# con-left-top.net
KiCad netlist of a schematic drawn in Altium Designer
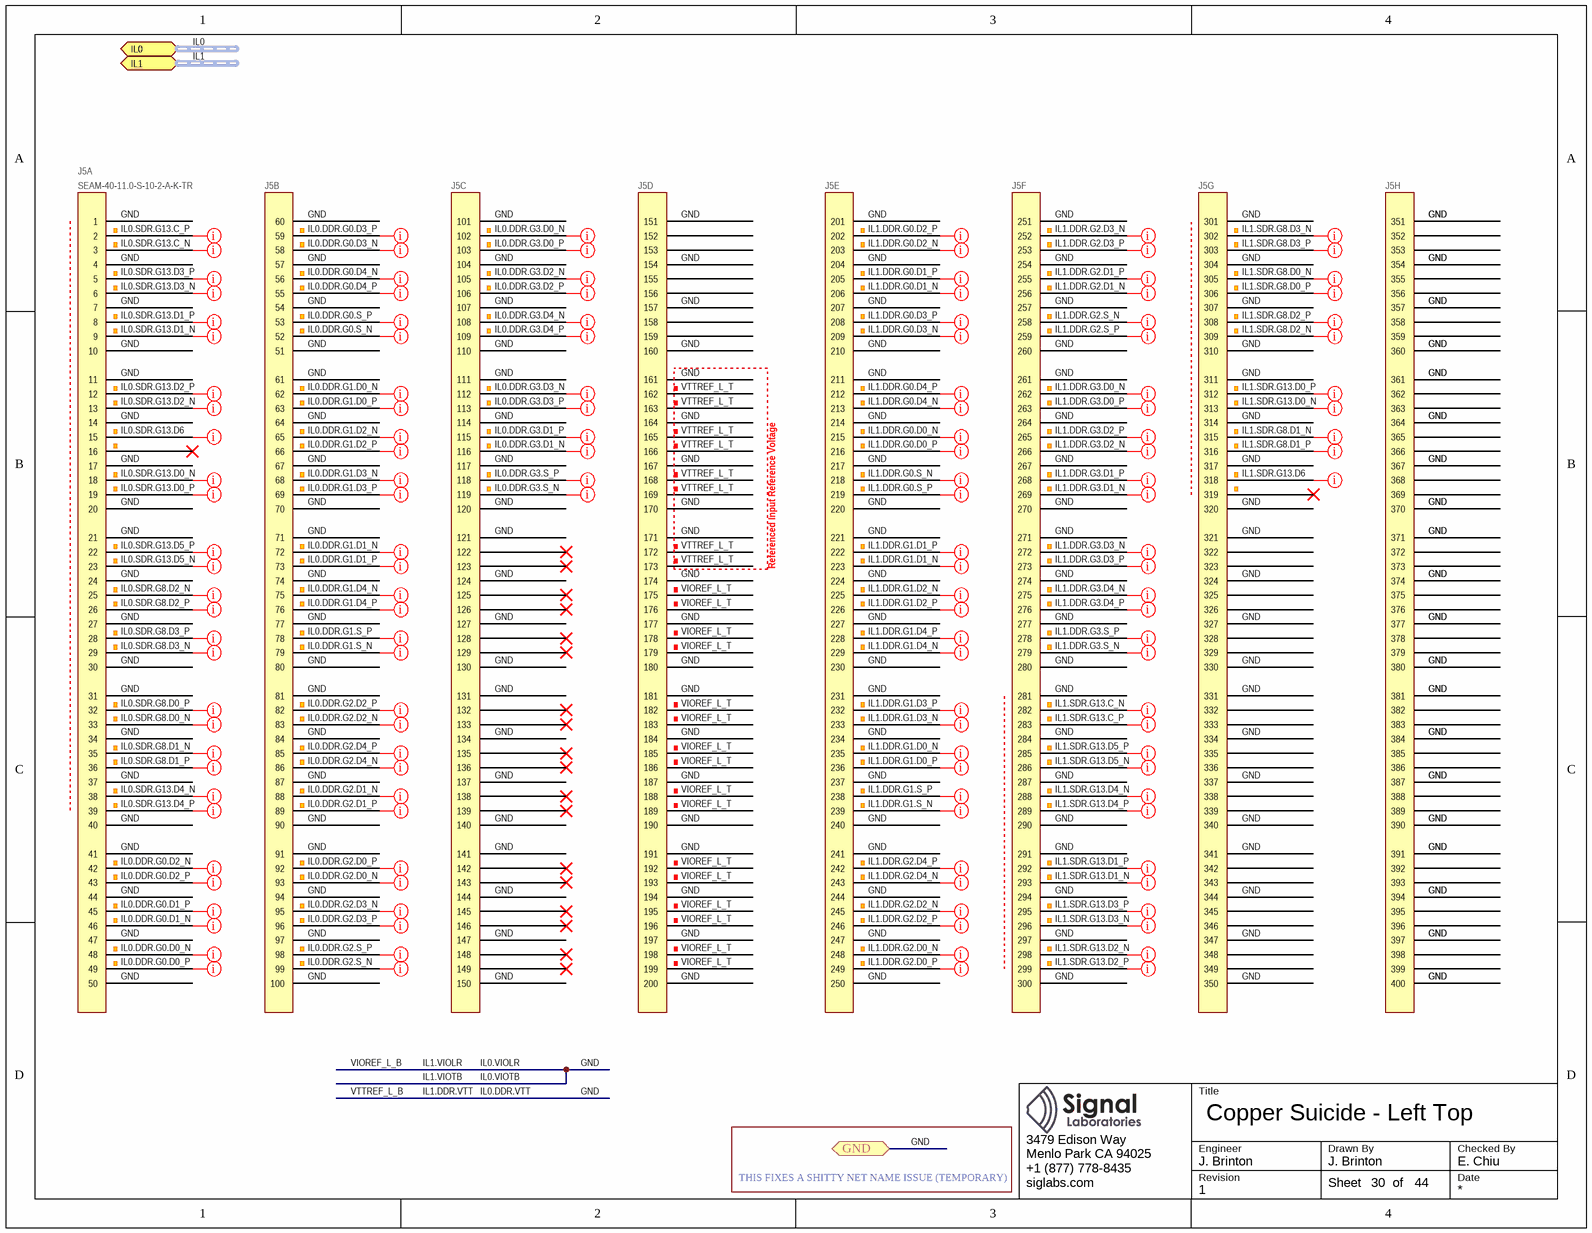
[diagram p0: con-left-top.SchDoc]

(export (version "E")
  (design (tool "Eeschema 10.0.6"))
  (components
    (comp (ref "J5")
      (value "SEAM-40-11.0-S-10-2-A-K-TR")
      (footprint "samtec:SEAM-40-11.0-S-10-2-A-K-TR")
      (description "Terminal Array Assembly, Surface Mount, 0.050\" Pitch, 400 Pins")
      (fields (field (name "MANUFACTURER") "Samtec"))
      (libsource (lib "samtec") (part "SEAM-40-11.0-S-10-2-A-K-TR"))
    )
  )
  (nets
    (net (code "3") (name "/GND") (class "Default")
      (node (ref "J5") (pin "1") (pinfunction "1_1") (pintype "passive"))
      (node (ref "J5") (pin "10") (pinfunction "10_10") (pintype "passive"))
      (node (ref "J5") (pin "100") (pinfunction "100_100") (pintype "passive"))
      (node (ref "J5") (pin "101") (pinfunction "101_101") (pintype "passive"))
      (node (ref "J5") (pin "104") (pinfunction "104_104") (pintype "passive"))
      (node (ref "J5") (pin "107") (pinfunction "107_107") (pintype "passive"))
      (node (ref "J5") (pin "11") (pinfunction "11_11") (pintype "passive"))
      (node (ref "J5") (pin "110") (pinfunction "110_110") (pintype "passive"))
      (node (ref "J5") (pin "111") (pinfunction "111_111") (pintype "passive"))
      (node (ref "J5") (pin "114") (pinfunction "114_114") (pintype "passive"))
      (node (ref "J5") (pin "117") (pinfunction "117_117") (pintype "passive"))
      (node (ref "J5") (pin "120") (pinfunction "120_120") (pintype "passive"))
      (node (ref "J5") (pin "121") (pinfunction "121_121") (pintype "passive"))
      (node (ref "J5") (pin "124") (pinfunction "124_124") (pintype "passive"))
      (node (ref "J5") (pin "127") (pinfunction "127_127") (pintype "passive"))
      (node (ref "J5") (pin "130") (pinfunction "130_130") (pintype "passive"))
      (node (ref "J5") (pin "131") (pinfunction "131_131") (pintype "passive"))
      (node (ref "J5") (pin "134") (pinfunction "134_134") (pintype "passive"))
      (node (ref "J5") (pin "137") (pinfunction "137_137") (pintype "passive"))
      (node (ref "J5") (pin "14") (pinfunction "14_14") (pintype "passive"))
      (node (ref "J5") (pin "140") (pinfunction "140_140") (pintype "passive"))
      (node (ref "J5") (pin "141") (pinfunction "141_141") (pintype "passive"))
      (node (ref "J5") (pin "144") (pinfunction "144_144") (pintype "passive"))
      (node (ref "J5") (pin "147") (pinfunction "147_147") (pintype "passive"))
      (node (ref "J5") (pin "150") (pinfunction "150_150") (pintype "passive"))
      (node (ref "J5") (pin "151") (pinfunction "151_151") (pintype "passive"))
      (node (ref "J5") (pin "154") (pinfunction "154_154") (pintype "passive"))
      (node (ref "J5") (pin "157") (pinfunction "157_157") (pintype "passive"))
      (node (ref "J5") (pin "160") (pinfunction "160_160") (pintype "passive"))
      (node (ref "J5") (pin "161") (pinfunction "161_161") (pintype "passive"))
      (node (ref "J5") (pin "164") (pinfunction "164_164") (pintype "passive"))
      (node (ref "J5") (pin "167") (pinfunction "167_167") (pintype "passive"))
      (node (ref "J5") (pin "17") (pinfunction "17_17") (pintype "passive"))
      (node (ref "J5") (pin "170") (pinfunction "170_170") (pintype "passive"))
      (node (ref "J5") (pin "171") (pinfunction "171_171") (pintype "passive"))
      (node (ref "J5") (pin "174") (pinfunction "174_174") (pintype "passive"))
      (node (ref "J5") (pin "177") (pinfunction "177_177") (pintype "passive"))
      (node (ref "J5") (pin "180") (pinfunction "180_180") (pintype "passive"))
      (node (ref "J5") (pin "181") (pinfunction "181_181") (pintype "passive"))
      (node (ref "J5") (pin "184") (pinfunction "184_184") (pintype "passive"))
      (node (ref "J5") (pin "187") (pinfunction "187_187") (pintype "passive"))
      (node (ref "J5") (pin "190") (pinfunction "190_190") (pintype "passive"))
      (node (ref "J5") (pin "191") (pinfunction "191_191") (pintype "passive"))
      (node (ref "J5") (pin "194") (pinfunction "194_194") (pintype "passive"))
      (node (ref "J5") (pin "197") (pinfunction "197_197") (pintype "passive"))
      (node (ref "J5") (pin "20") (pinfunction "20_20") (pintype "passive"))
      (node (ref "J5") (pin "200") (pinfunction "200_200") (pintype "passive"))
      (node (ref "J5") (pin "201") (pinfunction "201_201") (pintype "passive"))
      (node (ref "J5") (pin "204") (pinfunction "204_204") (pintype "passive"))
      (node (ref "J5") (pin "207") (pinfunction "207_207") (pintype "passive"))
      (node (ref "J5") (pin "21") (pinfunction "21_21") (pintype "passive"))
      (node (ref "J5") (pin "210") (pinfunction "210_210") (pintype "passive"))
      (node (ref "J5") (pin "211") (pinfunction "211_211") (pintype "passive"))
      (node (ref "J5") (pin "214") (pinfunction "214_214") (pintype "passive"))
      (node (ref "J5") (pin "217") (pinfunction "217_217") (pintype "passive"))
      (node (ref "J5") (pin "220") (pinfunction "220_220") (pintype "passive"))
      (node (ref "J5") (pin "221") (pinfunction "221_221") (pintype "passive"))
      (node (ref "J5") (pin "224") (pinfunction "224_224") (pintype "passive"))
      (node (ref "J5") (pin "227") (pinfunction "227_227") (pintype "passive"))
      (node (ref "J5") (pin "230") (pinfunction "230_230") (pintype "passive"))
      (node (ref "J5") (pin "231") (pinfunction "231_231") (pintype "passive"))
      (node (ref "J5") (pin "234") (pinfunction "234_234") (pintype "passive"))
      (node (ref "J5") (pin "237") (pinfunction "237_237") (pintype "passive"))
      (node (ref "J5") (pin "24") (pinfunction "24_24") (pintype "passive"))
      (node (ref "J5") (pin "240") (pinfunction "240_240") (pintype "passive"))
      (node (ref "J5") (pin "241") (pinfunction "241_241") (pintype "passive"))
      (node (ref "J5") (pin "244") (pinfunction "244_244") (pintype "passive"))
      (node (ref "J5") (pin "247") (pinfunction "247_247") (pintype "passive"))
      (node (ref "J5") (pin "250") (pinfunction "250_250") (pintype "passive"))
      (node (ref "J5") (pin "251") (pinfunction "251_251") (pintype "passive"))
      (node (ref "J5") (pin "254") (pinfunction "254_254") (pintype "passive"))
      (node (ref "J5") (pin "257") (pinfunction "257_257") (pintype "passive"))
      (node (ref "J5") (pin "260") (pinfunction "260_260") (pintype "passive"))
      (node (ref "J5") (pin "261") (pinfunction "261_261") (pintype "passive"))
      (node (ref "J5") (pin "264") (pinfunction "264_264") (pintype "passive"))
      (node (ref "J5") (pin "267") (pinfunction "267_267") (pintype "passive"))
      (node (ref "J5") (pin "27") (pinfunction "27_27") (pintype "passive"))
      (node (ref "J5") (pin "270") (pinfunction "270_270") (pintype "passive"))
      (node (ref "J5") (pin "271") (pinfunction "271_271") (pintype "passive"))
      (node (ref "J5") (pin "274") (pinfunction "274_274") (pintype "passive"))
      (node (ref "J5") (pin "277") (pinfunction "277_277") (pintype "passive"))
      (node (ref "J5") (pin "280") (pinfunction "280_280") (pintype "passive"))
      (node (ref "J5") (pin "281") (pinfunction "281_281") (pintype "passive"))
      (node (ref "J5") (pin "284") (pinfunction "284_284") (pintype "passive"))
      (node (ref "J5") (pin "287") (pinfunction "287_287") (pintype "passive"))
      (node (ref "J5") (pin "290") (pinfunction "290_290") (pintype "passive"))
      (node (ref "J5") (pin "291") (pinfunction "291_291") (pintype "passive"))
      (node (ref "J5") (pin "294") (pinfunction "294_294") (pintype "passive"))
      (node (ref "J5") (pin "297") (pinfunction "297_297") (pintype "passive"))
      (node (ref "J5") (pin "30") (pinfunction "30_30") (pintype "passive"))
      (node (ref "J5") (pin "300") (pinfunction "300_300") (pintype "passive"))
      (node (ref "J5") (pin "301") (pinfunction "301_301") (pintype "passive"))
      (node (ref "J5") (pin "304") (pinfunction "304_304") (pintype "passive"))
      (node (ref "J5") (pin "307") (pinfunction "307_307") (pintype "passive"))
      (node (ref "J5") (pin "31") (pinfunction "31_31") (pintype "passive"))
      (node (ref "J5") (pin "310") (pinfunction "310_310") (pintype "passive"))
      (node (ref "J5") (pin "311") (pinfunction "311_311") (pintype "passive"))
      (node (ref "J5") (pin "314") (pinfunction "314_314") (pintype "passive"))
      (node (ref "J5") (pin "317") (pinfunction "317_317") (pintype "passive"))
      (node (ref "J5") (pin "320") (pinfunction "320_320") (pintype "passive"))
      (node (ref "J5") (pin "321") (pinfunction "321_321") (pintype "passive"))
      (node (ref "J5") (pin "324") (pinfunction "324_324") (pintype "passive"))
      (node (ref "J5") (pin "327") (pinfunction "327_327") (pintype "passive"))
      (node (ref "J5") (pin "330") (pinfunction "330_330") (pintype "passive"))
      (node (ref "J5") (pin "331") (pinfunction "331_331") (pintype "passive"))
      (node (ref "J5") (pin "334") (pinfunction "334_334") (pintype "passive"))
      (node (ref "J5") (pin "337") (pinfunction "337_337") (pintype "passive"))
      (node (ref "J5") (pin "34") (pinfunction "34_34") (pintype "passive"))
      (node (ref "J5") (pin "340") (pinfunction "340_340") (pintype "passive"))
      (node (ref "J5") (pin "341") (pinfunction "341_341") (pintype "passive"))
      (node (ref "J5") (pin "344") (pinfunction "344_344") (pintype "passive"))
      (node (ref "J5") (pin "347") (pinfunction "347_347") (pintype "passive"))
      (node (ref "J5") (pin "350") (pinfunction "350_350") (pintype "passive"))
      (node (ref "J5") (pin "351") (pinfunction "351_351") (pintype "passive"))
      (node (ref "J5") (pin "354") (pinfunction "354_354") (pintype "passive"))
      (node (ref "J5") (pin "357") (pinfunction "357_357") (pintype "passive"))
      (node (ref "J5") (pin "360") (pinfunction "360_360") (pintype "passive"))
      (node (ref "J5") (pin "361") (pinfunction "361_361") (pintype "passive"))
      (node (ref "J5") (pin "364") (pinfunction "364_364") (pintype "passive"))
      (node (ref "J5") (pin "367") (pinfunction "367_367") (pintype "passive"))
      (node (ref "J5") (pin "37") (pinfunction "37_37") (pintype "passive"))
      (node (ref "J5") (pin "370") (pinfunction "370_370") (pintype "passive"))
      (node (ref "J5") (pin "371") (pinfunction "371_371") (pintype "passive"))
      (node (ref "J5") (pin "374") (pinfunction "374_374") (pintype "passive"))
      (node (ref "J5") (pin "377") (pinfunction "377_377") (pintype "passive"))
      (node (ref "J5") (pin "380") (pinfunction "380_380") (pintype "passive"))
      (node (ref "J5") (pin "381") (pinfunction "381_381") (pintype "passive"))
      (node (ref "J5") (pin "384") (pinfunction "384_384") (pintype "passive"))
      (node (ref "J5") (pin "387") (pinfunction "387_387") (pintype "passive"))
      (node (ref "J5") (pin "390") (pinfunction "390_390") (pintype "passive"))
      (node (ref "J5") (pin "391") (pinfunction "391_391") (pintype "passive"))
      (node (ref "J5") (pin "394") (pinfunction "394_394") (pintype "passive"))
      (node (ref "J5") (pin "397") (pinfunction "397_397") (pintype "passive"))
      (node (ref "J5") (pin "4") (pinfunction "4_4") (pintype "passive"))
      (node (ref "J5") (pin "40") (pinfunction "40_40") (pintype "passive"))
      (node (ref "J5") (pin "400") (pinfunction "400_400") (pintype "passive"))
      (node (ref "J5") (pin "41") (pinfunction "41_41") (pintype "passive"))
      (node (ref "J5") (pin "44") (pinfunction "44_44") (pintype "passive"))
      (node (ref "J5") (pin "47") (pinfunction "47_47") (pintype "passive"))
      (node (ref "J5") (pin "50") (pinfunction "50_50") (pintype "passive"))
      (node (ref "J5") (pin "51") (pinfunction "51_51") (pintype "passive"))
      (node (ref "J5") (pin "54") (pinfunction "54_54") (pintype "passive"))
      (node (ref "J5") (pin "57") (pinfunction "57_57") (pintype "passive"))
      (node (ref "J5") (pin "60") (pinfunction "60_60") (pintype "passive"))
      (node (ref "J5") (pin "61") (pinfunction "61_61") (pintype "passive"))
      (node (ref "J5") (pin "64") (pinfunction "64_64") (pintype "passive"))
      (node (ref "J5") (pin "67") (pinfunction "67_67") (pintype "passive"))
      (node (ref "J5") (pin "7") (pinfunction "7_7") (pintype "passive"))
      (node (ref "J5") (pin "70") (pinfunction "70_70") (pintype "passive"))
      (node (ref "J5") (pin "71") (pinfunction "71_71") (pintype "passive"))
      (node (ref "J5") (pin "74") (pinfunction "74_74") (pintype "passive"))
      (node (ref "J5") (pin "77") (pinfunction "77_77") (pintype "passive"))
      (node (ref "J5") (pin "80") (pinfunction "80_80") (pintype "passive"))
      (node (ref "J5") (pin "81") (pinfunction "81_81") (pintype "passive"))
      (node (ref "J5") (pin "84") (pinfunction "84_84") (pintype "passive"))
      (node (ref "J5") (pin "87") (pinfunction "87_87") (pintype "passive"))
      (node (ref "J5") (pin "90") (pinfunction "90_90") (pintype "passive"))
      (node (ref "J5") (pin "91") (pinfunction "91_91") (pintype "passive"))
      (node (ref "J5") (pin "94") (pinfunction "94_94") (pintype "passive"))
      (node (ref "J5") (pin "97") (pinfunction "97_97") (pintype "passive"))
    )
    (net (code "4") (name "/IL0.DDR.G0.D0_N") (class "Default")
      (node (ref "J5") (pin "48") (pinfunction "48_48") (pintype "passive"))
    )
    (net (code "5") (name "/IL0.DDR.G0.D0_P") (class "Default")
      (node (ref "J5") (pin "49") (pinfunction "49_49") (pintype "passive"))
    )
    (net (code "6") (name "/IL0.DDR.G0.D1_N") (class "Default")
      (node (ref "J5") (pin "46") (pinfunction "46_46") (pintype "passive"))
    )
    (net (code "7") (name "/IL0.DDR.G0.D1_P") (class "Default")
      (node (ref "J5") (pin "45") (pinfunction "45_45") (pintype "passive"))
    )
    (net (code "8") (name "/IL0.DDR.G0.D2_N") (class "Default")
      (node (ref "J5") (pin "42") (pinfunction "42_42") (pintype "passive"))
    )
    (net (code "9") (name "/IL0.DDR.G0.D2_P") (class "Default")
      (node (ref "J5") (pin "43") (pinfunction "43_43") (pintype "passive"))
    )
    (net (code "10") (name "/IL0.DDR.G0.D3_N") (class "Default")
      (node (ref "J5") (pin "58") (pinfunction "58_58") (pintype "passive"))
    )
    (net (code "11") (name "/IL0.DDR.G0.D3_P") (class "Default")
      (node (ref "J5") (pin "59") (pinfunction "59_59") (pintype "passive"))
    )
    (net (code "12") (name "/IL0.DDR.G0.D4_N") (class "Default")
      (node (ref "J5") (pin "56") (pinfunction "56_56") (pintype "passive"))
    )
    (net (code "13") (name "/IL0.DDR.G0.D4_P") (class "Default")
      (node (ref "J5") (pin "55") (pinfunction "55_55") (pintype "passive"))
    )
    (net (code "14") (name "/IL0.DDR.G0.S_N") (class "Default")
      (node (ref "J5") (pin "52") (pinfunction "52_52") (pintype "passive"))
    )
    (net (code "15") (name "/IL0.DDR.G0.S_P") (class "Default")
      (node (ref "J5") (pin "53") (pinfunction "53_53") (pintype "passive"))
    )
    (net (code "16") (name "/IL0.DDR.G1.D0_N") (class "Default")
      (node (ref "J5") (pin "62") (pinfunction "62_62") (pintype "passive"))
    )
    (net (code "17") (name "/IL0.DDR.G1.D0_P") (class "Default")
      (node (ref "J5") (pin "63") (pinfunction "63_63") (pintype "passive"))
    )
    (net (code "18") (name "/IL0.DDR.G1.D1_N") (class "Default")
      (node (ref "J5") (pin "72") (pinfunction "72_72") (pintype "passive"))
    )
    (net (code "19") (name "/IL0.DDR.G1.D1_P") (class "Default")
      (node (ref "J5") (pin "73") (pinfunction "73_73") (pintype "passive"))
    )
    (net (code "20") (name "/IL0.DDR.G1.D2_N") (class "Default")
      (node (ref "J5") (pin "65") (pinfunction "65_65") (pintype "passive"))
    )
    (net (code "21") (name "/IL0.DDR.G1.D2_P") (class "Default")
      (node (ref "J5") (pin "66") (pinfunction "66_66") (pintype "passive"))
    )
    (net (code "22") (name "/IL0.DDR.G1.D3_N") (class "Default")
      (node (ref "J5") (pin "68") (pinfunction "68_68") (pintype "passive"))
    )
    (net (code "23") (name "/IL0.DDR.G1.D3_P") (class "Default")
      (node (ref "J5") (pin "69") (pinfunction "69_69") (pintype "passive"))
    )
    (net (code "24") (name "/IL0.DDR.G1.D4_N") (class "Default")
      (node (ref "J5") (pin "75") (pinfunction "75_75") (pintype "passive"))
    )
    (net (code "25") (name "/IL0.DDR.G1.D4_P") (class "Default")
      (node (ref "J5") (pin "76") (pinfunction "76_76") (pintype "passive"))
    )
    (net (code "26") (name "/IL0.DDR.G1.S_N") (class "Default")
      (node (ref "J5") (pin "79") (pinfunction "79_79") (pintype "passive"))
    )
    (net (code "27") (name "/IL0.DDR.G1.S_P") (class "Default")
      (node (ref "J5") (pin "78") (pinfunction "78_78") (pintype "passive"))
    )
    (net (code "28") (name "/IL0.DDR.G2.D0_N") (class "Default")
      (node (ref "J5") (pin "93") (pinfunction "93_93") (pintype "passive"))
    )
    (net (code "29") (name "/IL0.DDR.G2.D0_P") (class "Default")
      (node (ref "J5") (pin "92") (pinfunction "92_92") (pintype "passive"))
    )
    (net (code "30") (name "/IL0.DDR.G2.D1_N") (class "Default")
      (node (ref "J5") (pin "88") (pinfunction "88_88") (pintype "passive"))
    )
    (net (code "31") (name "/IL0.DDR.G2.D1_P") (class "Default")
      (node (ref "J5") (pin "89") (pinfunction "89_89") (pintype "passive"))
    )
    (net (code "32") (name "/IL0.DDR.G2.D2_N") (class "Default")
      (node (ref "J5") (pin "83") (pinfunction "83_83") (pintype "passive"))
    )
    (net (code "33") (name "/IL0.DDR.G2.D2_P") (class "Default")
      (node (ref "J5") (pin "82") (pinfunction "82_82") (pintype "passive"))
    )
    (net (code "34") (name "/IL0.DDR.G2.D3_N") (class "Default")
      (node (ref "J5") (pin "95") (pinfunction "95_95") (pintype "passive"))
    )
    (net (code "35") (name "/IL0.DDR.G2.D3_P") (class "Default")
      (node (ref "J5") (pin "96") (pinfunction "96_96") (pintype "passive"))
    )
    (net (code "36") (name "/IL0.DDR.G2.D4_N") (class "Default")
      (node (ref "J5") (pin "86") (pinfunction "86_86") (pintype "passive"))
    )
    (net (code "37") (name "/IL0.DDR.G2.D4_P") (class "Default")
      (node (ref "J5") (pin "85") (pinfunction "85_85") (pintype "passive"))
    )
    (net (code "38") (name "/IL0.DDR.G2.S_N") (class "Default")
      (node (ref "J5") (pin "99") (pinfunction "99_99") (pintype "passive"))
    )
    (net (code "39") (name "/IL0.DDR.G2.S_P") (class "Default")
      (node (ref "J5") (pin "98") (pinfunction "98_98") (pintype "passive"))
    )
    (net (code "40") (name "/IL0.DDR.G3.D0_N") (class "Default")
      (node (ref "J5") (pin "102") (pinfunction "102_102") (pintype "passive"))
    )
    (net (code "41") (name "/IL0.DDR.G3.D0_P") (class "Default")
      (node (ref "J5") (pin "103") (pinfunction "103_103") (pintype "passive"))
    )
    (net (code "42") (name "/IL0.DDR.G3.D1_N") (class "Default")
      (node (ref "J5") (pin "116") (pinfunction "116_116") (pintype "passive"))
    )
    (net (code "43") (name "/IL0.DDR.G3.D1_P") (class "Default")
      (node (ref "J5") (pin "115") (pinfunction "115_115") (pintype "passive"))
    )
    (net (code "44") (name "/IL0.DDR.G3.D2_N") (class "Default")
      (node (ref "J5") (pin "105") (pinfunction "105_105") (pintype "passive"))
    )
    (net (code "45") (name "/IL0.DDR.G3.D2_P") (class "Default")
      (node (ref "J5") (pin "106") (pinfunction "106_106") (pintype "passive"))
    )
    (net (code "46") (name "/IL0.DDR.G3.D3_N") (class "Default")
      (node (ref "J5") (pin "112") (pinfunction "112_112") (pintype "passive"))
    )
    (net (code "47") (name "/IL0.DDR.G3.D3_P") (class "Default")
      (node (ref "J5") (pin "113") (pinfunction "113_113") (pintype "passive"))
    )
    (net (code "48") (name "/IL0.DDR.G3.D4_N") (class "Default")
      (node (ref "J5") (pin "108") (pinfunction "108_108") (pintype "passive"))
    )
    (net (code "49") (name "/IL0.DDR.G3.D4_P") (class "Default")
      (node (ref "J5") (pin "109") (pinfunction "109_109") (pintype "passive"))
    )
    (net (code "50") (name "/IL0.DDR.G3.S_N") (class "Default")
      (node (ref "J5") (pin "119") (pinfunction "119_119") (pintype "passive"))
    )
    (net (code "51") (name "/IL0.DDR.G3.S_P") (class "Default")
      (node (ref "J5") (pin "118") (pinfunction "118_118") (pintype "passive"))
    )
    (net (code "52") (name "/IL0.SDR.G8.D0_N") (class "Default")
      (node (ref "J5") (pin "33") (pinfunction "33_33") (pintype "passive"))
    )
    (net (code "53") (name "/IL0.SDR.G8.D0_P") (class "Default")
      (node (ref "J5") (pin "32") (pinfunction "32_32") (pintype "passive"))
    )
    (net (code "54") (name "/IL0.SDR.G8.D1_N") (class "Default")
      (node (ref "J5") (pin "35") (pinfunction "35_35") (pintype "passive"))
    )
    (net (code "55") (name "/IL0.SDR.G8.D1_P") (class "Default")
      (node (ref "J5") (pin "36") (pinfunction "36_36") (pintype "passive"))
    )
    (net (code "56") (name "/IL0.SDR.G8.D2_N") (class "Default")
      (node (ref "J5") (pin "25") (pinfunction "25_25") (pintype "passive"))
    )
    (net (code "57") (name "/IL0.SDR.G8.D2_P") (class "Default")
      (node (ref "J5") (pin "26") (pinfunction "26_26") (pintype "passive"))
    )
    (net (code "58") (name "/IL0.SDR.G8.D3_N") (class "Default")
      (node (ref "J5") (pin "29") (pinfunction "29_29") (pintype "passive"))
    )
    (net (code "59") (name "/IL0.SDR.G8.D3_P") (class "Default")
      (node (ref "J5") (pin "28") (pinfunction "28_28") (pintype "passive"))
    )
    (net (code "60") (name "/IL0.SDR.G13.C_N") (class "Default")
      (node (ref "J5") (pin "3") (pinfunction "3_3") (pintype "passive"))
    )
    (net (code "61") (name "/IL0.SDR.G13.C_P") (class "Default")
      (node (ref "J5") (pin "2") (pinfunction "2_2") (pintype "passive"))
    )
    (net (code "62") (name "/IL0.SDR.G13.D0_N") (class "Default")
      (node (ref "J5") (pin "18") (pinfunction "18_18") (pintype "passive"))
    )
    (net (code "63") (name "/IL0.SDR.G13.D0_P") (class "Default")
      (node (ref "J5") (pin "19") (pinfunction "19_19") (pintype "passive"))
    )
    (net (code "64") (name "/IL0.SDR.G13.D1_N") (class "Default")
      (node (ref "J5") (pin "9") (pinfunction "9_9") (pintype "passive"))
    )
    (net (code "65") (name "/IL0.SDR.G13.D1_P") (class "Default")
      (node (ref "J5") (pin "8") (pinfunction "8_8") (pintype "passive"))
    )
    (net (code "66") (name "/IL0.SDR.G13.D2_N") (class "Default")
      (node (ref "J5") (pin "13") (pinfunction "13_13") (pintype "passive"))
    )
    (net (code "67") (name "/IL0.SDR.G13.D2_P") (class "Default")
      (node (ref "J5") (pin "12") (pinfunction "12_12") (pintype "passive"))
    )
    (net (code "68") (name "/IL0.SDR.G13.D3_N") (class "Default")
      (node (ref "J5") (pin "6") (pinfunction "6_6") (pintype "passive"))
    )
    (net (code "69") (name "/IL0.SDR.G13.D3_P") (class "Default")
      (node (ref "J5") (pin "5") (pinfunction "5_5") (pintype "passive"))
    )
    (net (code "70") (name "/IL0.SDR.G13.D4_N") (class "Default")
      (node (ref "J5") (pin "38") (pinfunction "38_38") (pintype "passive"))
    )
    (net (code "71") (name "/IL0.SDR.G13.D4_P") (class "Default")
      (node (ref "J5") (pin "39") (pinfunction "39_39") (pintype "passive"))
    )
    (net (code "72") (name "/IL0.SDR.G13.D5_N") (class "Default")
      (node (ref "J5") (pin "23") (pinfunction "23_23") (pintype "passive"))
    )
    (net (code "73") (name "/IL0.SDR.G13.D5_P") (class "Default")
      (node (ref "J5") (pin "22") (pinfunction "22_22") (pintype "passive"))
    )
    (net (code "74") (name "/IL0.SDR.G13.D6") (class "Default")
      (node (ref "J5") (pin "15") (pinfunction "15_15") (pintype "passive"))
    )
    (net (code "75") (name "/IL1.DDR.G0.D0_N") (class "Default")
      (node (ref "J5") (pin "215") (pinfunction "215_215") (pintype "passive"))
    )
    (net (code "76") (name "/IL1.DDR.G0.D0_P") (class "Default")
      (node (ref "J5") (pin "216") (pinfunction "216_216") (pintype "passive"))
    )
    (net (code "77") (name "/IL1.DDR.G0.D1_N") (class "Default")
      (node (ref "J5") (pin "206") (pinfunction "206_206") (pintype "passive"))
    )
    (net (code "78") (name "/IL1.DDR.G0.D1_P") (class "Default")
      (node (ref "J5") (pin "205") (pinfunction "205_205") (pintype "passive"))
    )
    (net (code "79") (name "/IL1.DDR.G0.D2_N") (class "Default")
      (node (ref "J5") (pin "203") (pinfunction "203_203") (pintype "passive"))
    )
    (net (code "80") (name "/IL1.DDR.G0.D2_P") (class "Default")
      (node (ref "J5") (pin "202") (pinfunction "202_202") (pintype "passive"))
    )
    (net (code "81") (name "/IL1.DDR.G0.D3_N") (class "Default")
      (node (ref "J5") (pin "209") (pinfunction "209_209") (pintype "passive"))
    )
    (net (code "82") (name "/IL1.DDR.G0.D3_P") (class "Default")
      (node (ref "J5") (pin "208") (pinfunction "208_208") (pintype "passive"))
    )
    (net (code "83") (name "/IL1.DDR.G0.D4_N") (class "Default")
      (node (ref "J5") (pin "213") (pinfunction "213_213") (pintype "passive"))
    )
    (net (code "84") (name "/IL1.DDR.G0.D4_P") (class "Default")
      (node (ref "J5") (pin "212") (pinfunction "212_212") (pintype "passive"))
    )
    (net (code "85") (name "/IL1.DDR.G0.S_N") (class "Default")
      (node (ref "J5") (pin "218") (pinfunction "218_218") (pintype "passive"))
    )
    (net (code "86") (name "/IL1.DDR.G0.S_P") (class "Default")
      (node (ref "J5") (pin "219") (pinfunction "219_219") (pintype "passive"))
    )
    (net (code "87") (name "/IL1.DDR.G1.D0_N") (class "Default")
      (node (ref "J5") (pin "235") (pinfunction "235_235") (pintype "passive"))
    )
    (net (code "88") (name "/IL1.DDR.G1.D0_P") (class "Default")
      (node (ref "J5") (pin "236") (pinfunction "236_236") (pintype "passive"))
    )
    (net (code "89") (name "/IL1.DDR.G1.D1_N") (class "Default")
      (node (ref "J5") (pin "223") (pinfunction "223_223") (pintype "passive"))
    )
    (net (code "90") (name "/IL1.DDR.G1.D1_P") (class "Default")
      (node (ref "J5") (pin "222") (pinfunction "222_222") (pintype "passive"))
    )
    (net (code "91") (name "/IL1.DDR.G1.D2_N") (class "Default")
      (node (ref "J5") (pin "225") (pinfunction "225_225") (pintype "passive"))
    )
    (net (code "92") (name "/IL1.DDR.G1.D2_P") (class "Default")
      (node (ref "J5") (pin "226") (pinfunction "226_226") (pintype "passive"))
    )
    (net (code "93") (name "/IL1.DDR.G1.D3_N") (class "Default")
      (node (ref "J5") (pin "233") (pinfunction "233_233") (pintype "passive"))
    )
    (net (code "94") (name "/IL1.DDR.G1.D3_P") (class "Default")
      (node (ref "J5") (pin "232") (pinfunction "232_232") (pintype "passive"))
    )
    (net (code "95") (name "/IL1.DDR.G1.D4_N") (class "Default")
      (node (ref "J5") (pin "229") (pinfunction "229_229") (pintype "passive"))
    )
    (net (code "96") (name "/IL1.DDR.G1.D4_P") (class "Default")
      (node (ref "J5") (pin "228") (pinfunction "228_228") (pintype "passive"))
    )
    (net (code "97") (name "/IL1.DDR.G1.S_N") (class "Default")
      (node (ref "J5") (pin "239") (pinfunction "239_239") (pintype "passive"))
    )
    (net (code "98") (name "/IL1.DDR.G1.S_P") (class "Default")
      (node (ref "J5") (pin "238") (pinfunction "238_238") (pintype "passive"))
    )
    (net (code "99") (name "/IL1.DDR.G2.D0_N") (class "Default")
      (node (ref "J5") (pin "248") (pinfunction "248_248") (pintype "passive"))
    )
    (net (code "100") (name "/IL1.DDR.G2.D0_P") (class "Default")
      (node (ref "J5") (pin "249") (pinfunction "249_249") (pintype "passive"))
    )
    (net (code "101") (name "/IL1.DDR.G2.D1_N") (class "Default")
      (node (ref "J5") (pin "256") (pinfunction "256_256") (pintype "passive"))
    )
    (net (code "102") (name "/IL1.DDR.G2.D1_P") (class "Default")
      (node (ref "J5") (pin "255") (pinfunction "255_255") (pintype "passive"))
    )
    (net (code "103") (name "/IL1.DDR.G2.D2_N") (class "Default")
      (node (ref "J5") (pin "245") (pinfunction "245_245") (pintype "passive"))
    )
    (net (code "104") (name "/IL1.DDR.G2.D2_P") (class "Default")
      (node (ref "J5") (pin "246") (pinfunction "246_246") (pintype "passive"))
    )
    (net (code "105") (name "/IL1.DDR.G2.D3_N") (class "Default")
      (node (ref "J5") (pin "252") (pinfunction "252_252") (pintype "passive"))
    )
    (net (code "106") (name "/IL1.DDR.G2.D3_P") (class "Default")
      (node (ref "J5") (pin "253") (pinfunction "253_253") (pintype "passive"))
    )
    (net (code "107") (name "/IL1.DDR.G2.D4_N") (class "Default")
      (node (ref "J5") (pin "243") (pinfunction "243_243") (pintype "passive"))
    )
    (net (code "108") (name "/IL1.DDR.G2.D4_P") (class "Default")
      (node (ref "J5") (pin "242") (pinfunction "242_242") (pintype "passive"))
    )
    (net (code "109") (name "/IL1.DDR.G2.S_N") (class "Default")
      (node (ref "J5") (pin "258") (pinfunction "258_258") (pintype "passive"))
    )
    (net (code "110") (name "/IL1.DDR.G2.S_P") (class "Default")
      (node (ref "J5") (pin "259") (pinfunction "259_259") (pintype "passive"))
    )
    (net (code "111") (name "/IL1.DDR.G3.D0_N") (class "Default")
      (node (ref "J5") (pin "262") (pinfunction "262_262") (pintype "passive"))
    )
    (net (code "112") (name "/IL1.DDR.G3.D0_P") (class "Default")
      (node (ref "J5") (pin "263") (pinfunction "263_263") (pintype "passive"))
    )
    (net (code "113") (name "/IL1.DDR.G3.D1_N") (class "Default")
      (node (ref "J5") (pin "269") (pinfunction "269_269") (pintype "passive"))
    )
    (net (code "114") (name "/IL1.DDR.G3.D1_P") (class "Default")
      (node (ref "J5") (pin "268") (pinfunction "268_268") (pintype "passive"))
    )
    (net (code "115") (name "/IL1.DDR.G3.D2_N") (class "Default")
      (node (ref "J5") (pin "266") (pinfunction "266_266") (pintype "passive"))
    )
    (net (code "116") (name "/IL1.DDR.G3.D2_P") (class "Default")
      (node (ref "J5") (pin "265") (pinfunction "265_265") (pintype "passive"))
    )
    (net (code "117") (name "/IL1.DDR.G3.D3_N") (class "Default")
      (node (ref "J5") (pin "272") (pinfunction "272_272") (pintype "passive"))
    )
    (net (code "118") (name "/IL1.DDR.G3.D3_P") (class "Default")
      (node (ref "J5") (pin "273") (pinfunction "273_273") (pintype "passive"))
    )
    (net (code "119") (name "/IL1.DDR.G3.D4_N") (class "Default")
      (node (ref "J5") (pin "275") (pinfunction "275_275") (pintype "passive"))
    )
    (net (code "120") (name "/IL1.DDR.G3.D4_P") (class "Default")
      (node (ref "J5") (pin "276") (pinfunction "276_276") (pintype "passive"))
    )
    (net (code "121") (name "/IL1.DDR.G3.S_N") (class "Default")
      (node (ref "J5") (pin "279") (pinfunction "279_279") (pintype "passive"))
    )
    (net (code "122") (name "/IL1.DDR.G3.S_P") (class "Default")
      (node (ref "J5") (pin "278") (pinfunction "278_278") (pintype "passive"))
    )
    (net (code "123") (name "/IL1.SDR.G8.D0_N") (class "Default")
      (node (ref "J5") (pin "305") (pinfunction "305_305") (pintype "passive"))
    )
    (net (code "124") (name "/IL1.SDR.G8.D0_P") (class "Default")
      (node (ref "J5") (pin "306") (pinfunction "306_306") (pintype "passive"))
    )
    (net (code "125") (name "/IL1.SDR.G8.D1_N") (class "Default")
      (node (ref "J5") (pin "315") (pinfunction "315_315") (pintype "passive"))
    )
    (net (code "126") (name "/IL1.SDR.G8.D1_P") (class "Default")
      (node (ref "J5") (pin "316") (pinfunction "316_316") (pintype "passive"))
    )
    (net (code "127") (name "/IL1.SDR.G8.D2_N") (class "Default")
      (node (ref "J5") (pin "309") (pinfunction "309_309") (pintype "passive"))
    )
    (net (code "128") (name "/IL1.SDR.G8.D2_P") (class "Default")
      (node (ref "J5") (pin "308") (pinfunction "308_308") (pintype "passive"))
    )
    (net (code "129") (name "/IL1.SDR.G8.D3_N") (class "Default")
      (node (ref "J5") (pin "302") (pinfunction "302_302") (pintype "passive"))
    )
    (net (code "130") (name "/IL1.SDR.G8.D3_P") (class "Default")
      (node (ref "J5") (pin "303") (pinfunction "303_303") (pintype "passive"))
    )
    (net (code "131") (name "/IL1.SDR.G13.C_N") (class "Default")
      (node (ref "J5") (pin "282") (pinfunction "282_282") (pintype "passive"))
    )
    (net (code "132") (name "/IL1.SDR.G13.C_P") (class "Default")
      (node (ref "J5") (pin "283") (pinfunction "283_283") (pintype "passive"))
    )
    (net (code "133") (name "/IL1.SDR.G13.D0_N") (class "Default")
      (node (ref "J5") (pin "313") (pinfunction "313_313") (pintype "passive"))
    )
    (net (code "134") (name "/IL1.SDR.G13.D0_P") (class "Default")
      (node (ref "J5") (pin "312") (pinfunction "312_312") (pintype "passive"))
    )
    (net (code "135") (name "/IL1.SDR.G13.D1_N") (class "Default")
      (node (ref "J5") (pin "293") (pinfunction "293_293") (pintype "passive"))
    )
    (net (code "136") (name "/IL1.SDR.G13.D1_P") (class "Default")
      (node (ref "J5") (pin "292") (pinfunction "292_292") (pintype "passive"))
    )
    (net (code "137") (name "/IL1.SDR.G13.D2_N") (class "Default")
      (node (ref "J5") (pin "298") (pinfunction "298_298") (pintype "passive"))
    )
    (net (code "138") (name "/IL1.SDR.G13.D2_P") (class "Default")
      (node (ref "J5") (pin "299") (pinfunction "299_299") (pintype "passive"))
    )
    (net (code "139") (name "/IL1.SDR.G13.D3_N") (class "Default")
      (node (ref "J5") (pin "296") (pinfunction "296_296") (pintype "passive"))
    )
    (net (code "140") (name "/IL1.SDR.G13.D3_P") (class "Default")
      (node (ref "J5") (pin "295") (pinfunction "295_295") (pintype "passive"))
    )
    (net (code "141") (name "/IL1.SDR.G13.D4_N") (class "Default")
      (node (ref "J5") (pin "288") (pinfunction "288_288") (pintype "passive"))
    )
    (net (code "142") (name "/IL1.SDR.G13.D4_P") (class "Default")
      (node (ref "J5") (pin "289") (pinfunction "289_289") (pintype "passive"))
    )
    (net (code "143") (name "/IL1.SDR.G13.D5_N") (class "Default")
      (node (ref "J5") (pin "286") (pinfunction "286_286") (pintype "passive"))
    )
    (net (code "144") (name "/IL1.SDR.G13.D5_P") (class "Default")
      (node (ref "J5") (pin "285") (pinfunction "285_285") (pintype "passive"))
    )
    (net (code "145") (name "/IL1.SDR.G13.D6") (class "Default")
      (node (ref "J5") (pin "318") (pinfunction "318_318") (pintype "passive"))
    )
    (net (code "146") (name "/VIOREF_L_T") (class "Default")
      (node (ref "J5") (pin "175") (pinfunction "175_175") (pintype "passive"))
      (node (ref "J5") (pin "176") (pinfunction "176_176") (pintype "passive"))
      (node (ref "J5") (pin "178") (pinfunction "178_178") (pintype "passive"))
      (node (ref "J5") (pin "179") (pinfunction "179_179") (pintype "passive"))
      (node (ref "J5") (pin "182") (pinfunction "182_182") (pintype "passive"))
      (node (ref "J5") (pin "183") (pinfunction "183_183") (pintype "passive"))
      (node (ref "J5") (pin "185") (pinfunction "185_185") (pintype "passive"))
      (node (ref "J5") (pin "186") (pinfunction "186_186") (pintype "passive"))
      (node (ref "J5") (pin "188") (pinfunction "188_188") (pintype "passive"))
      (node (ref "J5") (pin "189") (pinfunction "189_189") (pintype "passive"))
      (node (ref "J5") (pin "192") (pinfunction "192_192") (pintype "passive"))
      (node (ref "J5") (pin "193") (pinfunction "193_193") (pintype "passive"))
      (node (ref "J5") (pin "195") (pinfunction "195_195") (pintype "passive"))
      (node (ref "J5") (pin "196") (pinfunction "196_196") (pintype "passive"))
      (node (ref "J5") (pin "198") (pinfunction "198_198") (pintype "passive"))
      (node (ref "J5") (pin "199") (pinfunction "199_199") (pintype "passive"))
    )
    (net (code "147") (name "/VTTREF_L_T") (class "Default")
      (node (ref "J5") (pin "162") (pinfunction "162_162") (pintype "passive"))
      (node (ref "J5") (pin "163") (pinfunction "163_163") (pintype "passive"))
      (node (ref "J5") (pin "165") (pinfunction "165_165") (pintype "passive"))
      (node (ref "J5") (pin "166") (pinfunction "166_166") (pintype "passive"))
      (node (ref "J5") (pin "168") (pinfunction "168_168") (pintype "passive"))
      (node (ref "J5") (pin "169") (pinfunction "169_169") (pintype "passive"))
      (node (ref "J5") (pin "172") (pinfunction "172_172") (pintype "passive"))
      (node (ref "J5") (pin "173") (pinfunction "173_173") (pintype "passive"))
    )
    (net (code "150") (name "unconnected-(J5-Pad16)") (class "Default")
      (node (ref "J5") (pin "16") (pinfunction "16_16") (pintype "passive+no_connect"))
    )
    (net (code "151") (name "unconnected-(J5-Pad122)") (class "Default")
      (node (ref "J5") (pin "122") (pinfunction "122_122") (pintype "passive+no_connect"))
    )
    (net (code "152") (name "unconnected-(J5-Pad123)") (class "Default")
      (node (ref "J5") (pin "123") (pinfunction "123_123") (pintype "passive+no_connect"))
    )
    (net (code "153") (name "unconnected-(J5-Pad125)") (class "Default")
      (node (ref "J5") (pin "125") (pinfunction "125_125") (pintype "passive+no_connect"))
    )
    (net (code "154") (name "unconnected-(J5-Pad126)") (class "Default")
      (node (ref "J5") (pin "126") (pinfunction "126_126") (pintype "passive+no_connect"))
    )
    (net (code "155") (name "unconnected-(J5-Pad128)") (class "Default")
      (node (ref "J5") (pin "128") (pinfunction "128_128") (pintype "passive+no_connect"))
    )
    (net (code "156") (name "unconnected-(J5-Pad129)") (class "Default")
      (node (ref "J5") (pin "129") (pinfunction "129_129") (pintype "passive+no_connect"))
    )
    (net (code "157") (name "unconnected-(J5-Pad132)") (class "Default")
      (node (ref "J5") (pin "132") (pinfunction "132_132") (pintype "passive+no_connect"))
    )
    (net (code "158") (name "unconnected-(J5-Pad133)") (class "Default")
      (node (ref "J5") (pin "133") (pinfunction "133_133") (pintype "passive+no_connect"))
    )
    (net (code "159") (name "unconnected-(J5-Pad135)") (class "Default")
      (node (ref "J5") (pin "135") (pinfunction "135_135") (pintype "passive+no_connect"))
    )
    (net (code "160") (name "unconnected-(J5-Pad136)") (class "Default")
      (node (ref "J5") (pin "136") (pinfunction "136_136") (pintype "passive+no_connect"))
    )
    (net (code "161") (name "unconnected-(J5-Pad138)") (class "Default")
      (node (ref "J5") (pin "138") (pinfunction "138_138") (pintype "passive+no_connect"))
    )
    (net (code "162") (name "unconnected-(J5-Pad139)") (class "Default")
      (node (ref "J5") (pin "139") (pinfunction "139_139") (pintype "passive+no_connect"))
    )
    (net (code "163") (name "unconnected-(J5-Pad142)") (class "Default")
      (node (ref "J5") (pin "142") (pinfunction "142_142") (pintype "passive+no_connect"))
    )
    (net (code "164") (name "unconnected-(J5-Pad143)") (class "Default")
      (node (ref "J5") (pin "143") (pinfunction "143_143") (pintype "passive+no_connect"))
    )
    (net (code "165") (name "unconnected-(J5-Pad145)") (class "Default")
      (node (ref "J5") (pin "145") (pinfunction "145_145") (pintype "passive+no_connect"))
    )
    (net (code "166") (name "unconnected-(J5-Pad146)") (class "Default")
      (node (ref "J5") (pin "146") (pinfunction "146_146") (pintype "passive+no_connect"))
    )
    (net (code "167") (name "unconnected-(J5-Pad148)") (class "Default")
      (node (ref "J5") (pin "148") (pinfunction "148_148") (pintype "passive+no_connect"))
    )
    (net (code "168") (name "unconnected-(J5-Pad149)") (class "Default")
      (node (ref "J5") (pin "149") (pinfunction "149_149") (pintype "passive+no_connect"))
    )
    (net (code "169") (name "unconnected-(J5-Pad152)") (class "Default")
      (node (ref "J5") (pin "152") (pinfunction "152_152") (pintype "passive"))
    )
    (net (code "170") (name "unconnected-(J5-Pad153)") (class "Default")
      (node (ref "J5") (pin "153") (pinfunction "153_153") (pintype "passive"))
    )
    (net (code "171") (name "unconnected-(J5-Pad155)") (class "Default")
      (node (ref "J5") (pin "155") (pinfunction "155_155") (pintype "passive"))
    )
    (net (code "172") (name "unconnected-(J5-Pad156)") (class "Default")
      (node (ref "J5") (pin "156") (pinfunction "156_156") (pintype "passive"))
    )
    (net (code "173") (name "unconnected-(J5-Pad158)") (class "Default")
      (node (ref "J5") (pin "158") (pinfunction "158_158") (pintype "passive"))
    )
    (net (code "174") (name "unconnected-(J5-Pad159)") (class "Default")
      (node (ref "J5") (pin "159") (pinfunction "159_159") (pintype "passive"))
    )
    (net (code "175") (name "unconnected-(J5-Pad319)") (class "Default")
      (node (ref "J5") (pin "319") (pinfunction "319_319") (pintype "passive+no_connect"))
    )
    (net (code "176") (name "unconnected-(J5-Pad322)") (class "Default")
      (node (ref "J5") (pin "322") (pinfunction "322_322") (pintype "passive"))
    )
    (net (code "177") (name "unconnected-(J5-Pad323)") (class "Default")
      (node (ref "J5") (pin "323") (pinfunction "323_323") (pintype "passive"))
    )
    (net (code "178") (name "unconnected-(J5-Pad325)") (class "Default")
      (node (ref "J5") (pin "325") (pinfunction "325_325") (pintype "passive"))
    )
    (net (code "179") (name "unconnected-(J5-Pad326)") (class "Default")
      (node (ref "J5") (pin "326") (pinfunction "326_326") (pintype "passive"))
    )
    (net (code "180") (name "unconnected-(J5-Pad328)") (class "Default")
      (node (ref "J5") (pin "328") (pinfunction "328_328") (pintype "passive"))
    )
    (net (code "181") (name "unconnected-(J5-Pad329)") (class "Default")
      (node (ref "J5") (pin "329") (pinfunction "329_329") (pintype "passive"))
    )
    (net (code "182") (name "unconnected-(J5-Pad332)") (class "Default")
      (node (ref "J5") (pin "332") (pinfunction "332_332") (pintype "passive"))
    )
    (net (code "183") (name "unconnected-(J5-Pad333)") (class "Default")
      (node (ref "J5") (pin "333") (pinfunction "333_333") (pintype "passive"))
    )
    (net (code "184") (name "unconnected-(J5-Pad335)") (class "Default")
      (node (ref "J5") (pin "335") (pinfunction "335_335") (pintype "passive"))
    )
    (net (code "185") (name "unconnected-(J5-Pad336)") (class "Default")
      (node (ref "J5") (pin "336") (pinfunction "336_336") (pintype "passive"))
    )
    (net (code "186") (name "unconnected-(J5-Pad338)") (class "Default")
      (node (ref "J5") (pin "338") (pinfunction "338_338") (pintype "passive"))
    )
    (net (code "187") (name "unconnected-(J5-Pad339)") (class "Default")
      (node (ref "J5") (pin "339") (pinfunction "339_339") (pintype "passive"))
    )
    (net (code "188") (name "unconnected-(J5-Pad342)") (class "Default")
      (node (ref "J5") (pin "342") (pinfunction "342_342") (pintype "passive"))
    )
    (net (code "189") (name "unconnected-(J5-Pad343)") (class "Default")
      (node (ref "J5") (pin "343") (pinfunction "343_343") (pintype "passive"))
    )
    (net (code "190") (name "unconnected-(J5-Pad345)") (class "Default")
      (node (ref "J5") (pin "345") (pinfunction "345_345") (pintype "passive"))
    )
    (net (code "191") (name "unconnected-(J5-Pad346)") (class "Default")
      (node (ref "J5") (pin "346") (pinfunction "346_346") (pintype "passive"))
    )
    (net (code "192") (name "unconnected-(J5-Pad348)") (class "Default")
      (node (ref "J5") (pin "348") (pinfunction "348_348") (pintype "passive"))
    )
    (net (code "193") (name "unconnected-(J5-Pad349)") (class "Default")
      (node (ref "J5") (pin "349") (pinfunction "349_349") (pintype "passive"))
    )
    (net (code "194") (name "unconnected-(J5-Pad352)") (class "Default")
      (node (ref "J5") (pin "352") (pinfunction "352_352") (pintype "passive"))
    )
    (net (code "195") (name "unconnected-(J5-Pad353)") (class "Default")
      (node (ref "J5") (pin "353") (pinfunction "353_353") (pintype "passive"))
    )
    (net (code "196") (name "unconnected-(J5-Pad355)") (class "Default")
      (node (ref "J5") (pin "355") (pinfunction "355_355") (pintype "passive"))
    )
    (net (code "197") (name "unconnected-(J5-Pad356)") (class "Default")
      (node (ref "J5") (pin "356") (pinfunction "356_356") (pintype "passive"))
    )
    (net (code "198") (name "unconnected-(J5-Pad358)") (class "Default")
      (node (ref "J5") (pin "358") (pinfunction "358_358") (pintype "passive"))
    )
    (net (code "199") (name "unconnected-(J5-Pad359)") (class "Default")
      (node (ref "J5") (pin "359") (pinfunction "359_359") (pintype "passive"))
    )
    (net (code "200") (name "unconnected-(J5-Pad362)") (class "Default")
      (node (ref "J5") (pin "362") (pinfunction "362_362") (pintype "passive"))
    )
    (net (code "201") (name "unconnected-(J5-Pad363)") (class "Default")
      (node (ref "J5") (pin "363") (pinfunction "363_363") (pintype "passive"))
    )
    (net (code "202") (name "unconnected-(J5-Pad365)") (class "Default")
      (node (ref "J5") (pin "365") (pinfunction "365_365") (pintype "passive"))
    )
    (net (code "203") (name "unconnected-(J5-Pad366)") (class "Default")
      (node (ref "J5") (pin "366") (pinfunction "366_366") (pintype "passive"))
    )
    (net (code "204") (name "unconnected-(J5-Pad368)") (class "Default")
      (node (ref "J5") (pin "368") (pinfunction "368_368") (pintype "passive"))
    )
    (net (code "205") (name "unconnected-(J5-Pad369)") (class "Default")
      (node (ref "J5") (pin "369") (pinfunction "369_369") (pintype "passive"))
    )
    (net (code "206") (name "unconnected-(J5-Pad372)") (class "Default")
      (node (ref "J5") (pin "372") (pinfunction "372_372") (pintype "passive"))
    )
    (net (code "207") (name "unconnected-(J5-Pad373)") (class "Default")
      (node (ref "J5") (pin "373") (pinfunction "373_373") (pintype "passive"))
    )
    (net (code "208") (name "unconnected-(J5-Pad375)") (class "Default")
      (node (ref "J5") (pin "375") (pinfunction "375_375") (pintype "passive"))
    )
    (net (code "209") (name "unconnected-(J5-Pad376)") (class "Default")
      (node (ref "J5") (pin "376") (pinfunction "376_376") (pintype "passive"))
    )
    (net (code "210") (name "unconnected-(J5-Pad378)") (class "Default")
      (node (ref "J5") (pin "378") (pinfunction "378_378") (pintype "passive"))
    )
    (net (code "211") (name "unconnected-(J5-Pad379)") (class "Default")
      (node (ref "J5") (pin "379") (pinfunction "379_379") (pintype "passive"))
    )
    (net (code "212") (name "unconnected-(J5-Pad382)") (class "Default")
      (node (ref "J5") (pin "382") (pinfunction "382_382") (pintype "passive"))
    )
    (net (code "213") (name "unconnected-(J5-Pad383)") (class "Default")
      (node (ref "J5") (pin "383") (pinfunction "383_383") (pintype "passive"))
    )
    (net (code "214") (name "unconnected-(J5-Pad385)") (class "Default")
      (node (ref "J5") (pin "385") (pinfunction "385_385") (pintype "passive"))
    )
    (net (code "215") (name "unconnected-(J5-Pad386)") (class "Default")
      (node (ref "J5") (pin "386") (pinfunction "386_386") (pintype "passive"))
    )
    (net (code "216") (name "unconnected-(J5-Pad388)") (class "Default")
      (node (ref "J5") (pin "388") (pinfunction "388_388") (pintype "passive"))
    )
    (net (code "217") (name "unconnected-(J5-Pad389)") (class "Default")
      (node (ref "J5") (pin "389") (pinfunction "389_389") (pintype "passive"))
    )
    (net (code "218") (name "unconnected-(J5-Pad392)") (class "Default")
      (node (ref "J5") (pin "392") (pinfunction "392_392") (pintype "passive"))
    )
    (net (code "219") (name "unconnected-(J5-Pad393)") (class "Default")
      (node (ref "J5") (pin "393") (pinfunction "393_393") (pintype "passive"))
    )
    (net (code "220") (name "unconnected-(J5-Pad395)") (class "Default")
      (node (ref "J5") (pin "395") (pinfunction "395_395") (pintype "passive"))
    )
    (net (code "221") (name "unconnected-(J5-Pad396)") (class "Default")
      (node (ref "J5") (pin "396") (pinfunction "396_396") (pintype "passive"))
    )
    (net (code "222") (name "unconnected-(J5-Pad398)") (class "Default")
      (node (ref "J5") (pin "398") (pinfunction "398_398") (pintype "passive"))
    )
    (net (code "223") (name "unconnected-(J5-Pad399)") (class "Default")
      (node (ref "J5") (pin "399") (pinfunction "399_399") (pintype "passive"))
    )
  )
)
